# ppc_cpld.net
KiCad netlist of a schematic drawn in Altium Designer
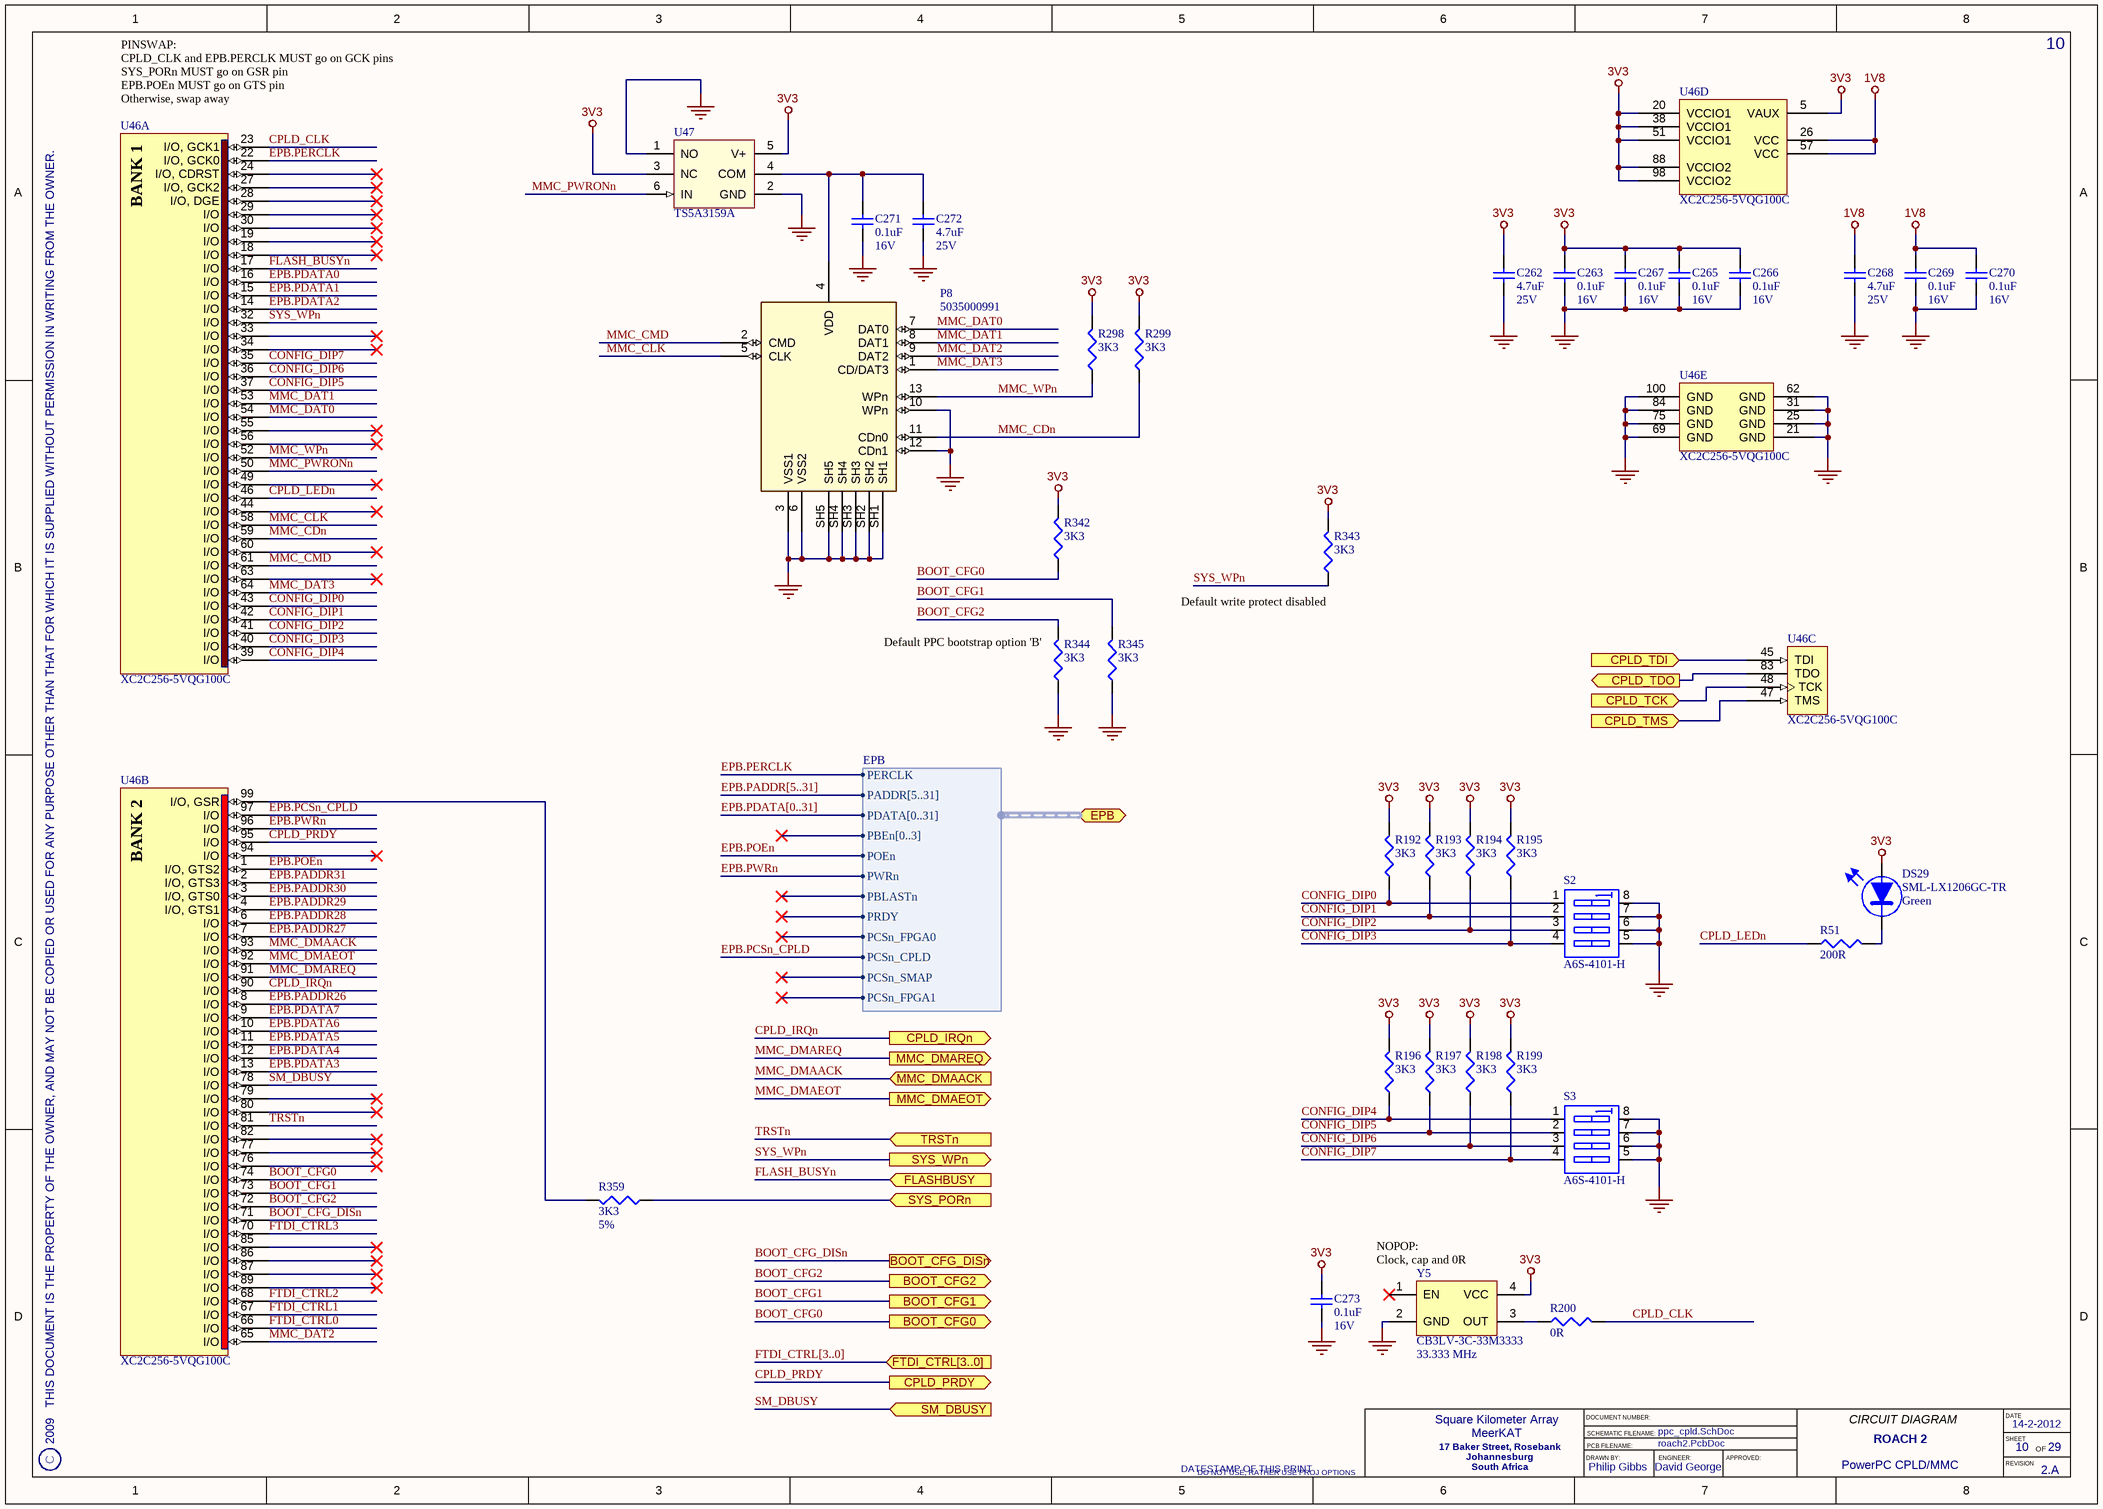
[diagram p0: ppc_cpld.SchDoc]

(export (version "E")
  (design (tool "Eeschema 10.0.6"))
  (components
    (comp (ref "C262")
      (value "4.7uF")
      (footprint "CAPC2012X127L")
      (description "4.7uF, Ceramic Capacitor")
      (fields
        (field (name "RATING") "25V")
        (field (name "MANUFACTURER") "MURATA")
        (field (name "PARTNUM") "GRM21BR61E475KA12K")
      )
      (libsource (lib "altium_db") (part "CapStd"))
    )
    (comp (ref "C263")
      (value "0.1uF")
      (footprint "CAPC1005X60L")
      (description "0.1uF, Ceramic Capacitor")
      (fields
        (field (name "RATING") "16V")
        (field (name "MANUFACTURER") "VENKEL")
        (field (name "PARTNUM") "C0402X7R160-104KN")
      )
      (libsource (lib "altium_db") (part "CapStd"))
    )
    (comp (ref "C265")
      (value "0.1uF")
      (footprint "CAPC1005X60L")
      (description "0.1uF, Ceramic Capacitor")
      (fields
        (field (name "RATING") "16V")
        (field (name "MANUFACTURER") "VENKEL")
        (field (name "PARTNUM") "C0402X7R160-104KN")
      )
      (libsource (lib "altium_db") (part "CapStd"))
    )
    (comp (ref "C266")
      (value "0.1uF")
      (footprint "CAPC1005X60L")
      (description "0.1uF, Ceramic Capacitor")
      (fields
        (field (name "RATING") "16V")
        (field (name "MANUFACTURER") "VENKEL")
        (field (name "PARTNUM") "C0402X7R160-104KN")
      )
      (libsource (lib "altium_db") (part "CapStd"))
    )
    (comp (ref "C267")
      (value "0.1uF")
      (footprint "CAPC1005X60L")
      (description "0.1uF, Ceramic Capacitor")
      (fields
        (field (name "RATING") "16V")
        (field (name "MANUFACTURER") "VENKEL")
        (field (name "PARTNUM") "C0402X7R160-104KN")
      )
      (libsource (lib "altium_db") (part "CapStd"))
    )
    (comp (ref "C268")
      (value "4.7uF")
      (footprint "CAPC2012X127L")
      (description "4.7uF, Ceramic Capacitor")
      (fields
        (field (name "RATING") "25V")
        (field (name "MANUFACTURER") "MURATA")
        (field (name "PARTNUM") "GRM21BR61E475KA12K")
      )
      (libsource (lib "altium_db") (part "CapStd"))
    )
    (comp (ref "C269")
      (value "0.1uF")
      (footprint "CAPC1005X60L")
      (description "0.1uF, Ceramic Capacitor")
      (fields
        (field (name "RATING") "16V")
        (field (name "MANUFACTURER") "VENKEL")
        (field (name "PARTNUM") "C0402X7R160-104KN")
      )
      (libsource (lib "altium_db") (part "CapStd"))
    )
    (comp (ref "C270")
      (value "0.1uF")
      (footprint "CAPC1005X60L")
      (description "0.1uF, Ceramic Capacitor")
      (fields
        (field (name "RATING") "16V")
        (field (name "MANUFACTURER") "VENKEL")
        (field (name "PARTNUM") "C0402X7R160-104KN")
      )
      (libsource (lib "altium_db") (part "CapStd"))
    )
    (comp (ref "C271")
      (value "0.1uF")
      (footprint "CAPC1005X60L")
      (description "0.1uF, Ceramic Capacitor")
      (fields
        (field (name "RATING") "16V")
        (field (name "MANUFACTURER") "VENKEL")
        (field (name "PARTNUM") "C0402X7R160-104KN")
      )
      (libsource (lib "altium_db") (part "CapStd"))
    )
    (comp (ref "C272")
      (value "4.7uF")
      (footprint "CAPC2012X127L")
      (description "4.7uF, Ceramic Capacitor")
      (fields
        (field (name "RATING") "25V")
        (field (name "MANUFACTURER") "MURATA")
        (field (name "PARTNUM") "GRM21BR61E475KA12K")
      )
      (libsource (lib "altium_db") (part "CapStd"))
    )
    (comp (ref "C273")
      (value "0.1uF")
      (footprint "CAPC1005X60L")
      (description "0.1uF, Ceramic Capacitor")
      (fields
        (field (name "RATING") "16V")
        (field (name "MANUFACTURER") "VENKEL")
        (field (name "PARTNUM") "C0402X7R160-104KN")
      )
      (libsource (lib "altium_db") (part "CapStd"))
    )
    (comp (ref "DS29")
      (value "SML-LX1206GC-TR")
      (footprint "LEDC3216X120N")
      (description "Green, Surface mount, LED, 1206")
      (fields (field (name "COLOUR") "Green") (field (name "MANUFACTURER") "LUMEX"))
      (libsource (lib "altium_db") (part "LEDSTD"))
    )
    (comp (ref "P8")
      (value "5035000991")
      (footprint "MOLEX_5035000991")
      (description "Push/Push SD Card Connector with Card Detection")
      (fields (field (name "PARTNUM") "5035000991") (field (name "MANUFACTURER") "Molex"))
      (libsource (lib "altium_db") (part "MOLEX_5035000991"))
    )
    (comp (ref "R51")
      (value "200R")
      (footprint "RESC1005X40L")
      (description "200R, 1.1mm x 0.5mm, Thick Film Resistor")
      (fields (field (name "MANUFACTURER") "ROYALOHM") (field (name "PARTNUM") "0402WGF0201T1E"))
      (libsource (lib "altium_db") (part "ResStd"))
    )
    (comp (ref "R192")
      (value "3K3")
      (footprint "RESC1005X40L")
      (description "3K3, 1.1mm x 0.5mm, Thick Film Resistor")
      (fields (field (name "MANUFACTURER") "ROYALOHM") (field (name "PARTNUM") "0402WGJ0332T1E"))
      (libsource (lib "altium_db") (part "ResStd"))
    )
    (comp (ref "R193")
      (value "3K3")
      (footprint "RESC1005X40L")
      (description "3K3, 1.1mm x 0.5mm, Thick Film Resistor")
      (fields (field (name "MANUFACTURER") "ROYALOHM") (field (name "PARTNUM") "0402WGJ0332T1E"))
      (libsource (lib "altium_db") (part "ResStd"))
    )
    (comp (ref "R194")
      (value "3K3")
      (footprint "RESC1005X40L")
      (description "3K3, 1.1mm x 0.5mm, Thick Film Resistor")
      (fields (field (name "MANUFACTURER") "ROYALOHM") (field (name "PARTNUM") "0402WGJ0332T1E"))
      (libsource (lib "altium_db") (part "ResStd"))
    )
    (comp (ref "R195")
      (value "3K3")
      (footprint "RESC1005X40L")
      (description "3K3, 1.1mm x 0.5mm, Thick Film Resistor")
      (fields (field (name "MANUFACTURER") "ROYALOHM") (field (name "PARTNUM") "0402WGJ0332T1E"))
      (libsource (lib "altium_db") (part "ResStd"))
    )
    (comp (ref "R196")
      (value "3K3")
      (footprint "RESC1005X40L")
      (description "3K3, 1.1mm x 0.5mm, Thick Film Resistor")
      (fields (field (name "MANUFACTURER") "ROYALOHM") (field (name "PARTNUM") "0402WGJ0332T1E"))
      (libsource (lib "altium_db") (part "ResStd"))
    )
    (comp (ref "R197")
      (value "3K3")
      (footprint "RESC1005X40L")
      (description "3K3, 1.1mm x 0.5mm, Thick Film Resistor")
      (fields (field (name "MANUFACTURER") "ROYALOHM") (field (name "PARTNUM") "0402WGJ0332T1E"))
      (libsource (lib "altium_db") (part "ResStd"))
    )
    (comp (ref "R198")
      (value "3K3")
      (footprint "RESC1005X40L")
      (description "3K3, 1.1mm x 0.5mm, Thick Film Resistor")
      (fields (field (name "MANUFACTURER") "ROYALOHM") (field (name "PARTNUM") "0402WGJ0332T1E"))
      (libsource (lib "altium_db") (part "ResStd"))
    )
    (comp (ref "R199")
      (value "3K3")
      (footprint "RESC1005X40L")
      (description "3K3, 1.1mm x 0.5mm, Thick Film Resistor")
      (fields (field (name "MANUFACTURER") "ROYALOHM") (field (name "PARTNUM") "0402WGJ0332T1E"))
      (libsource (lib "altium_db") (part "ResStd"))
    )
    (comp (ref "R200")
      (value "0R")
      (footprint "RESC1005X40L")
      (description "0R, 1.1mm x 0.5mm, Thick Film Resistor")
      (fields (field (name "MANUFACTURER") "ROYALOHM") (field (name "PARTNUM") "0402WG00000T1E"))
      (libsource (lib "altium_db") (part "ResStd"))
    )
    (comp (ref "R298")
      (value "3K3")
      (footprint "RESC1005X40L")
      (description "3K3, 1.1mm x 0.5mm, Thick Film Resistor")
      (fields (field (name "MANUFACTURER") "ROYALOHM") (field (name "PARTNUM") "0402WGJ0332T1E"))
      (libsource (lib "altium_db") (part "ResStd"))
    )
    (comp (ref "R299")
      (value "3K3")
      (footprint "RESC1005X40L")
      (description "3K3, 1.1mm x 0.5mm, Thick Film Resistor")
      (fields (field (name "MANUFACTURER") "ROYALOHM") (field (name "PARTNUM") "0402WGJ0332T1E"))
      (libsource (lib "altium_db") (part "ResStd"))
    )
    (comp (ref "R342")
      (value "3K3")
      (footprint "RESC1005X40L")
      (description "3K3, 1.1mm x 0.5mm, Thick Film Resistor")
      (fields (field (name "MANUFACTURER") "ROYALOHM") (field (name "PARTNUM") "0402WGJ0332T1E"))
      (libsource (lib "altium_db") (part "ResStd"))
    )
    (comp (ref "R343")
      (value "3K3")
      (footprint "RESC1005X40L")
      (description "3K3, 1.1mm x 0.5mm, Thick Film Resistor")
      (fields (field (name "MANUFACTURER") "ROYALOHM") (field (name "PARTNUM") "0402WGJ0332T1E"))
      (libsource (lib "altium_db") (part "ResStd"))
    )
    (comp (ref "R344")
      (value "3K3")
      (footprint "RESC1005X40L")
      (description "3K3, 1.1mm x 0.5mm, Thick Film Resistor")
      (fields (field (name "MANUFACTURER") "ROYALOHM") (field (name "PARTNUM") "0402WGJ0332T1E"))
      (libsource (lib "altium_db") (part "ResStd"))
    )
    (comp (ref "R345")
      (value "3K3")
      (footprint "RESC1005X40L")
      (description "3K3, 1.1mm x 0.5mm, Thick Film Resistor")
      (fields (field (name "MANUFACTURER") "ROYALOHM") (field (name "PARTNUM") "0402WGJ0332T1E"))
      (libsource (lib "altium_db") (part "ResStd"))
    )
    (comp (ref "R359")
      (value "3K3")
      (footprint "RESC1005X40L")
      (description "3K3, 1.1mm x 0.5mm, Thick Film Resistor")
      (fields
        (field (name "MANUFACTURER") "ROYALOHM")
        (field (name "PARTNUM") "0402WGJ0332T1E")
        (field (name "TOLERANCE") "5%")
      )
      (libsource (lib "altium_db") (part "ResStd"))
    )
    (comp (ref "S2")
      (value "A6S-4101-H")
      (footprint "A6S-4101-H")
      (description "4-Input, Surface mount, DIP Switch")
      (fields (field (name "PARTNUM") "A6S-4101-H") (field (name "MANUFACTURER") "OMRON"))
      (libsource (lib "altium_db") (part "A6S-4101-H"))
    )
    (comp (ref "S3")
      (value "A6S-4101-H")
      (footprint "A6S-4101-H")
      (description "4-Input, Surface mount, DIP Switch")
      (fields (field (name "PARTNUM") "A6S-4101-H") (field (name "MANUFACTURER") "OMRON"))
      (libsource (lib "altium_db") (part "A6S-4101-H"))
    )
    (comp (ref "U46")
      (value "XC2C256-5VQG100C")
      (footprint "VQG100_L")
      (description "CoolRunner-II, 1.8V, 256 Macrocell CPLD, 100-Pin VQFP, Pb-Free, Commercial Grade")
      (fields (field (name "MANUFACTURER") "Xilinx"))
      (libsource (lib "altium_db") (part "XC2C256-5VQG100C"))
    )
    (comp (ref "U47")
      (value "TS5A3159A")
      (footprint "SOT23-6")
      (description "6-pin 1 Ohm analogue switch")
      (fields (field (name "MANUFACTURER") "Texas Instruments"))
      (libsource (lib "altium_db") (part "TS5A3159A"))
    )
    (comp (ref "Y5")
      (value "CB3LV-3C-33M3333")
      (footprint "CB3X-X-XMX")
      (description "Surface mount, 33.3333 MHz, 3V3 Clock, oscillator")
      (fields
        (field (name "PARTNUM") "CB3LV-3C-33M3333")
        (field (name "FREQUENCY") "33.333 MHz")
        (field (name "MANUFACTURER") "CTS")
      )
      (libsource (lib "altium_db") (part "CB3LV-3C-33M3333"))
    )
  )
  (nets
    (net (code "48") (name "/BOOT_CFG0") (class "Default")
      (node (ref "R342") (pin "1") (pinfunction "1_1") (pintype "passive"))
      (node (ref "U46") (pin "74") (pinfunction "I/O_74") (pintype "bidirectional"))
    )
    (net (code "49") (name "/BOOT_CFG1") (class "Default")
      (node (ref "R345") (pin "2") (pinfunction "2_2") (pintype "passive"))
      (node (ref "U46") (pin "73") (pinfunction "I/O_73") (pintype "bidirectional"))
    )
    (net (code "50") (name "/BOOT_CFG2") (class "Default")
      (node (ref "R344") (pin "2") (pinfunction "2_2") (pintype "passive"))
      (node (ref "U46") (pin "72") (pinfunction "I/O_72") (pintype "bidirectional"))
    )
    (net (code "51") (name "/BOOT_CFG_DISn") (class "Default")
      (node (ref "U46") (pin "71") (pinfunction "I/O_71") (pintype "bidirectional"))
    )
    (net (code "52") (name "/CONFIG_DIP0") (class "Default")
      (node (ref "R192") (pin "1") (pinfunction "1_1") (pintype "passive"))
      (node (ref "S2") (pin "1") (pinfunction "SW1A_1") (pintype "passive"))
      (node (ref "U46") (pin "43") (pinfunction "I/O_43") (pintype "bidirectional"))
    )
    (net (code "53") (name "/CONFIG_DIP1") (class "Default")
      (node (ref "R193") (pin "1") (pinfunction "1_1") (pintype "passive"))
      (node (ref "S2") (pin "2") (pinfunction "SW2A_2") (pintype "passive"))
      (node (ref "U46") (pin "42") (pinfunction "I/O_42") (pintype "bidirectional"))
    )
    (net (code "54") (name "/CONFIG_DIP2") (class "Default")
      (node (ref "R194") (pin "1") (pinfunction "1_1") (pintype "passive"))
      (node (ref "S2") (pin "3") (pinfunction "SW3A_3") (pintype "passive"))
      (node (ref "U46") (pin "41") (pinfunction "I/O_41") (pintype "bidirectional"))
    )
    (net (code "55") (name "/CONFIG_DIP3") (class "Default")
      (node (ref "R195") (pin "1") (pinfunction "1_1") (pintype "passive"))
      (node (ref "S2") (pin "4") (pinfunction "SW4A_4") (pintype "passive"))
      (node (ref "U46") (pin "40") (pinfunction "I/O_40") (pintype "bidirectional"))
    )
    (net (code "56") (name "/CONFIG_DIP4") (class "Default")
      (node (ref "R196") (pin "1") (pinfunction "1_1") (pintype "passive"))
      (node (ref "S3") (pin "1") (pinfunction "SW1A_1") (pintype "passive"))
      (node (ref "U46") (pin "39") (pinfunction "I/O_39") (pintype "bidirectional"))
    )
    (net (code "57") (name "/CONFIG_DIP5") (class "Default")
      (node (ref "R197") (pin "1") (pinfunction "1_1") (pintype "passive"))
      (node (ref "S3") (pin "2") (pinfunction "SW2A_2") (pintype "passive"))
      (node (ref "U46") (pin "37") (pinfunction "I/O_37") (pintype "bidirectional"))
    )
    (net (code "58") (name "/CONFIG_DIP6") (class "Default")
      (node (ref "R198") (pin "1") (pinfunction "1_1") (pintype "passive"))
      (node (ref "S3") (pin "3") (pinfunction "SW3A_3") (pintype "passive"))
      (node (ref "U46") (pin "36") (pinfunction "I/O_36") (pintype "bidirectional"))
    )
    (net (code "59") (name "/CONFIG_DIP7") (class "Default")
      (node (ref "R199") (pin "1") (pinfunction "1_1") (pintype "passive"))
      (node (ref "S3") (pin "4") (pinfunction "SW4A_4") (pintype "passive"))
      (node (ref "U46") (pin "35") (pinfunction "I/O_35") (pintype "bidirectional"))
    )
    (net (code "60") (name "/CPLD_CLK") (class "Default")
      (node (ref "R200") (pin "2") (pinfunction "2_2") (pintype "passive"))
      (node (ref "U46") (pin "23") (pinfunction "I/O,_GCK1_23") (pintype "bidirectional"))
    )
    (net (code "61") (name "/CPLD_IRQn") (class "Default")
      (node (ref "U46") (pin "90") (pinfunction "I/O_90") (pintype "bidirectional"))
    )
    (net (code "62") (name "/CPLD_LEDn") (class "Default")
      (node (ref "R51") (pin "1") (pinfunction "1_1") (pintype "passive"))
      (node (ref "U46") (pin "46") (pinfunction "I/O_46") (pintype "bidirectional"))
    )
    (net (code "63") (name "/CPLD_PRDY") (class "Default")
      (node (ref "U46") (pin "95") (pinfunction "I/O_95") (pintype "bidirectional"))
    )
    (net (code "64") (name "/CPLD_TCK") (class "Default")
      (node (ref "U46") (pin "48") (pinfunction "TCK_48") (pintype "input"))
    )
    (net (code "65") (name "/CPLD_TDI") (class "Default")
      (node (ref "U46") (pin "45") (pinfunction "TDI_45") (pintype "input"))
    )
    (net (code "66") (name "/CPLD_TDO") (class "Default")
      (node (ref "U46") (pin "83") (pinfunction "TDO_83") (pintype "passive"))
    )
    (net (code "67") (name "/CPLD_TMS") (class "Default")
      (node (ref "U46") (pin "47") (pinfunction "TMS_47") (pintype "input"))
    )
    (net (code "68") (name "/EPB.PADDR26") (class "Default")
      (node (ref "U46") (pin "8") (pinfunction "I/O_8") (pintype "bidirectional"))
    )
    (net (code "69") (name "/EPB.PADDR27") (class "Default")
      (node (ref "U46") (pin "7") (pinfunction "I/O_7") (pintype "bidirectional"))
    )
    (net (code "70") (name "/EPB.PADDR28") (class "Default")
      (node (ref "U46") (pin "6") (pinfunction "I/O_6") (pintype "bidirectional"))
    )
    (net (code "71") (name "/EPB.PADDR29") (class "Default")
      (node (ref "U46") (pin "4") (pinfunction "I/O,_GTS1_4") (pintype "bidirectional"))
    )
    (net (code "72") (name "/EPB.PADDR30") (class "Default")
      (node (ref "U46") (pin "3") (pinfunction "I/O,_GTS0_3") (pintype "bidirectional"))
    )
    (net (code "73") (name "/EPB.PADDR31") (class "Default")
      (node (ref "U46") (pin "2") (pinfunction "I/O,_GTS3_2") (pintype "bidirectional"))
    )
    (net (code "75") (name "/EPB.PCSn_CPLD") (class "Default")
      (node (ref "U46") (pin "97") (pinfunction "I/O_97") (pintype "bidirectional"))
    )
    (net (code "76") (name "/EPB.PDATA0") (class "Default")
      (node (ref "U46") (pin "16") (pinfunction "I/O_16") (pintype "bidirectional"))
    )
    (net (code "77") (name "/EPB.PDATA1") (class "Default")
      (node (ref "U46") (pin "15") (pinfunction "I/O_15") (pintype "bidirectional"))
    )
    (net (code "78") (name "/EPB.PDATA2") (class "Default")
      (node (ref "U46") (pin "14") (pinfunction "I/O_14") (pintype "bidirectional"))
    )
    (net (code "79") (name "/EPB.PDATA3") (class "Default")
      (node (ref "U46") (pin "13") (pinfunction "I/O_13") (pintype "bidirectional"))
    )
    (net (code "80") (name "/EPB.PDATA4") (class "Default")
      (node (ref "U46") (pin "12") (pinfunction "I/O_12") (pintype "bidirectional"))
    )
    (net (code "81") (name "/EPB.PDATA5") (class "Default")
      (node (ref "U46") (pin "11") (pinfunction "I/O_11") (pintype "bidirectional"))
    )
    (net (code "82") (name "/EPB.PDATA6") (class "Default")
      (node (ref "U46") (pin "10") (pinfunction "I/O_10") (pintype "bidirectional"))
    )
    (net (code "83") (name "/EPB.PDATA7") (class "Default")
      (node (ref "U46") (pin "9") (pinfunction "I/O_9") (pintype "bidirectional"))
    )
    (net (code "85") (name "/EPB.PERCLK") (class "Default")
      (node (ref "U46") (pin "22") (pinfunction "I/O,_GCK0_22") (pintype "bidirectional"))
    )
    (net (code "86") (name "/EPB.POEn") (class "Default")
      (node (ref "U46") (pin "1") (pinfunction "I/O,_GTS2_1") (pintype "bidirectional"))
    )
    (net (code "87") (name "/EPB.PWRn") (class "Default")
      (node (ref "U46") (pin "96") (pinfunction "I/O_96") (pintype "bidirectional"))
    )
    (net (code "89") (name "/FLASH_BUSYn") (class "Default")
      (node (ref "U46") (pin "17") (pinfunction "I/O_17") (pintype "bidirectional"))
    )
    (net (code "90") (name "/FTDI_CTRL0") (class "Default")
      (node (ref "U46") (pin "66") (pinfunction "I/O_66") (pintype "bidirectional"))
    )
    (net (code "91") (name "/FTDI_CTRL1") (class "Default")
      (node (ref "U46") (pin "67") (pinfunction "I/O_67") (pintype "bidirectional"))
    )
    (net (code "92") (name "/FTDI_CTRL2") (class "Default")
      (node (ref "U46") (pin "68") (pinfunction "I/O_68") (pintype "bidirectional"))
    )
    (net (code "93") (name "/FTDI_CTRL3") (class "Default")
      (node (ref "U46") (pin "70") (pinfunction "I/O_70") (pintype "bidirectional"))
    )
    (net (code "95") (name "/MMC_CDn") (class "Default")
      (node (ref "P8") (pin "11") (pinfunction "CDn0_11") (pintype "bidirectional"))
      (node (ref "R299") (pin "1") (pinfunction "1_1") (pintype "passive"))
      (node (ref "U46") (pin "59") (pinfunction "I/O_59") (pintype "bidirectional"))
    )
    (net (code "96") (name "/MMC_CLK") (class "Default")
      (node (ref "P8") (pin "5") (pinfunction "CLK_5") (pintype "bidirectional"))
      (node (ref "U46") (pin "58") (pinfunction "I/O_58") (pintype "bidirectional"))
    )
    (net (code "97") (name "/MMC_CMD") (class "Default")
      (node (ref "P8") (pin "2") (pinfunction "CMD_2") (pintype "bidirectional"))
      (node (ref "U46") (pin "61") (pinfunction "I/O_61") (pintype "bidirectional"))
    )
    (net (code "98") (name "/MMC_DAT0") (class "Default")
      (node (ref "P8") (pin "7") (pinfunction "DAT0_7") (pintype "bidirectional"))
      (node (ref "U46") (pin "54") (pinfunction "I/O_54") (pintype "bidirectional"))
    )
    (net (code "99") (name "/MMC_DAT1") (class "Default")
      (node (ref "P8") (pin "8") (pinfunction "DAT1_8") (pintype "bidirectional"))
      (node (ref "U46") (pin "53") (pinfunction "I/O_53") (pintype "bidirectional"))
    )
    (net (code "100") (name "/MMC_DAT2") (class "Default")
      (node (ref "P8") (pin "9") (pinfunction "DAT2_9") (pintype "bidirectional"))
      (node (ref "U46") (pin "65") (pinfunction "I/O_65") (pintype "bidirectional"))
    )
    (net (code "101") (name "/MMC_DAT3") (class "Default")
      (node (ref "P8") (pin "1") (pinfunction "CD/DAT3_1") (pintype "bidirectional"))
      (node (ref "U46") (pin "64") (pinfunction "I/O_64") (pintype "bidirectional"))
    )
    (net (code "102") (name "/MMC_DMAACK") (class "Default")
      (node (ref "U46") (pin "93") (pinfunction "I/O_93") (pintype "bidirectional"))
    )
    (net (code "103") (name "/MMC_DMAEOT") (class "Default")
      (node (ref "U46") (pin "92") (pinfunction "I/O_92") (pintype "bidirectional"))
    )
    (net (code "104") (name "/MMC_DMAREQ") (class "Default")
      (node (ref "U46") (pin "91") (pinfunction "I/O_91") (pintype "bidirectional"))
    )
    (net (code "105") (name "/MMC_PWRONn") (class "Default")
      (node (ref "U46") (pin "50") (pinfunction "I/O_50") (pintype "bidirectional"))
      (node (ref "U47") (pin "6") (pinfunction "IN_6") (pintype "input"))
    )
    (net (code "106") (name "/MMC_WPn") (class "Default")
      (node (ref "P8") (pin "13") (pinfunction "WPn_13") (pintype "bidirectional"))
      (node (ref "R298") (pin "1") (pinfunction "1_1") (pintype "passive"))
      (node (ref "U46") (pin "52") (pinfunction "I/O_52") (pintype "bidirectional"))
    )
    (net (code "107") (name "/SM_DBUSY") (class "Default")
      (node (ref "U46") (pin "78") (pinfunction "I/O_78") (pintype "bidirectional"))
    )
    (net (code "108") (name "/SYS_PORn") (class "Default")
      (node (ref "R359") (pin "1") (pinfunction "1_1") (pintype "passive"))
    )
    (net (code "109") (name "/SYS_WPn") (class "Default")
      (node (ref "R343") (pin "1") (pinfunction "1_1") (pintype "passive"))
      (node (ref "U46") (pin "32") (pinfunction "I/O_32") (pintype "bidirectional"))
    )
    (net (code "110") (name "/TRSTn") (class "Default")
      (node (ref "U46") (pin "81") (pinfunction "I/O_81") (pintype "bidirectional"))
    )
    (net (code "112") (name "1V8") (class "Default")
      (node (ref "C268") (pin "2") (pinfunction "2_2") (pintype "passive"))
      (node (ref "C269") (pin "2") (pinfunction "2_2") (pintype "passive"))
      (node (ref "C270") (pin "2") (pinfunction "2_2") (pintype "passive"))
      (node (ref "U46") (pin "26") (pinfunction "VCC_26") (pintype "power_in"))
      (node (ref "U46") (pin "57") (pinfunction "VCC_57") (pintype "power_in"))
    )
    (net (code "113") (name "3V3") (class "Default")
      (node (ref "C262") (pin "2") (pinfunction "2_2") (pintype "passive"))
      (node (ref "C263") (pin "2") (pinfunction "2_2") (pintype "passive"))
      (node (ref "C265") (pin "2") (pinfunction "2_2") (pintype "passive"))
      (node (ref "C266") (pin "2") (pinfunction "2_2") (pintype "passive"))
      (node (ref "C267") (pin "2") (pinfunction "2_2") (pintype "passive"))
      (node (ref "C273") (pin "2") (pinfunction "2_2") (pintype "passive"))
      (node (ref "DS29") (pin "2") (pinfunction "A_2") (pintype "passive"))
      (node (ref "R192") (pin "2") (pinfunction "2_2") (pintype "passive"))
      (node (ref "R193") (pin "2") (pinfunction "2_2") (pintype "passive"))
      (node (ref "R194") (pin "2") (pinfunction "2_2") (pintype "passive"))
      (node (ref "R195") (pin "2") (pinfunction "2_2") (pintype "passive"))
      (node (ref "R196") (pin "2") (pinfunction "2_2") (pintype "passive"))
      (node (ref "R197") (pin "2") (pinfunction "2_2") (pintype "passive"))
      (node (ref "R198") (pin "2") (pinfunction "2_2") (pintype "passive"))
      (node (ref "R199") (pin "2") (pinfunction "2_2") (pintype "passive"))
      (node (ref "R298") (pin "2") (pinfunction "2_2") (pintype "passive"))
      (node (ref "R299") (pin "2") (pinfunction "2_2") (pintype "passive"))
      (node (ref "R342") (pin "2") (pinfunction "2_2") (pintype "passive"))
      (node (ref "R343") (pin "2") (pinfunction "2_2") (pintype "passive"))
      (node (ref "U46") (pin "20") (pinfunction "VCCIO1_20") (pintype "power_in"))
      (node (ref "U46") (pin "38") (pinfunction "VCCIO1_38") (pintype "power_in"))
      (node (ref "U46") (pin "5") (pinfunction "VAUX_5") (pintype "power_in"))
      (node (ref "U46") (pin "51") (pinfunction "VCCIO1_51") (pintype "power_in"))
      (node (ref "U46") (pin "88") (pinfunction "VCCIO2_88") (pintype "power_in"))
      (node (ref "U46") (pin "98") (pinfunction "VCCIO2_98") (pintype "power_in"))
      (node (ref "U47") (pin "3") (pinfunction "NC_3") (pintype "passive"))
      (node (ref "U47") (pin "5") (pinfunction "V+_5") (pintype "passive"))
      (node (ref "Y5") (pin "4") (pinfunction "VCC_4") (pintype "passive"))
    )
    (net (code "114") (name "GND") (class "Default")
      (node (ref "C262") (pin "1") (pinfunction "1_1") (pintype "passive"))
      (node (ref "C263") (pin "1") (pinfunction "1_1") (pintype "passive"))
      (node (ref "C265") (pin "1") (pinfunction "1_1") (pintype "passive"))
      (node (ref "C266") (pin "1") (pinfunction "1_1") (pintype "passive"))
      (node (ref "C267") (pin "1") (pinfunction "1_1") (pintype "passive"))
      (node (ref "C268") (pin "1") (pinfunction "1_1") (pintype "passive"))
      (node (ref "C269") (pin "1") (pinfunction "1_1") (pintype "passive"))
      (node (ref "C270") (pin "1") (pinfunction "1_1") (pintype "passive"))
      (node (ref "C271") (pin "1") (pinfunction "1_1") (pintype "passive"))
      (node (ref "C272") (pin "1") (pinfunction "1_1") (pintype "passive"))
      (node (ref "C273") (pin "1") (pinfunction "1_1") (pintype "passive"))
      (node (ref "P8") (pin "10") (pinfunction "WPn_10") (pintype "bidirectional"))
      (node (ref "P8") (pin "12") (pinfunction "CDn1_12") (pintype "bidirectional"))
      (node (ref "P8") (pin "3") (pinfunction "VSS1_3") (pintype "power_in"))
      (node (ref "P8") (pin "6") (pinfunction "VSS2_6") (pintype "power_in"))
      (node (ref "P8") (pin "SH1") (pinfunction "SH1_SH1") (pintype "power_in"))
      (node (ref "P8") (pin "SH2") (pinfunction "SH2_SH2") (pintype "power_in"))
      (node (ref "P8") (pin "SH3") (pinfunction "SH3_SH3") (pintype "power_in"))
      (node (ref "P8") (pin "SH4") (pinfunction "SH4_SH4") (pintype "power_in"))
      (node (ref "P8") (pin "SH5") (pinfunction "SH5_SH5") (pintype "power_in"))
      (node (ref "R344") (pin "1") (pinfunction "1_1") (pintype "passive"))
      (node (ref "R345") (pin "1") (pinfunction "1_1") (pintype "passive"))
      (node (ref "S2") (pin "5") (pinfunction "SW4B_5") (pintype "passive"))
      (node (ref "S2") (pin "6") (pinfunction "SW3B_6") (pintype "passive"))
      (node (ref "S2") (pin "7") (pinfunction "SW2B_7") (pintype "passive"))
      (node (ref "S2") (pin "8") (pinfunction "SW1B_8") (pintype "passive"))
      (node (ref "S3") (pin "5") (pinfunction "SW4B_5") (pintype "passive"))
      (node (ref "S3") (pin "6") (pinfunction "SW3B_6") (pintype "passive"))
      (node (ref "S3") (pin "7") (pinfunction "SW2B_7") (pintype "passive"))
      (node (ref "S3") (pin "8") (pinfunction "SW1B_8") (pintype "passive"))
      (node (ref "U46") (pin "100") (pinfunction "GND_100") (pintype "power_in"))
      (node (ref "U46") (pin "21") (pinfunction "GND_21") (pintype "power_in"))
      (node (ref "U46") (pin "25") (pinfunction "GND_25") (pintype "power_in"))
      (node (ref "U46") (pin "31") (pinfunction "GND_31") (pintype "power_in"))
      (node (ref "U46") (pin "62") (pinfunction "GND_62") (pintype "power_in"))
      (node (ref "U46") (pin "69") (pinfunction "GND_69") (pintype "power_in"))
      (node (ref "U46") (pin "75") (pinfunction "GND_75") (pintype "power_in"))
      (node (ref "U46") (pin "84") (pinfunction "GND_84") (pintype "power_in"))
      (node (ref "U47") (pin "1") (pinfunction "NO_1") (pintype "passive"))
      (node (ref "U47") (pin "2") (pinfunction "GND_2") (pintype "passive"))
      (node (ref "Y5") (pin "2") (pinfunction "GND_2") (pintype "passive"))
    )
    (net (code "115") (name "Net-(DS29-K)") (class "Default")
      (node (ref "DS29") (pin "1") (pinfunction "K_1") (pintype "passive"))
      (node (ref "R51") (pin "2") (pinfunction "2_2") (pintype "passive"))
    )
    (net (code "116") (name "Net-(P8-VDD)") (class "Default")
      (node (ref "C271") (pin "2") (pinfunction "2_2") (pintype "passive"))
      (node (ref "C272") (pin "2") (pinfunction "2_2") (pintype "passive"))
      (node (ref "P8") (pin "4") (pinfunction "VDD_4") (pintype "power_in"))
      (node (ref "U47") (pin "4") (pinfunction "COM_4") (pintype "passive"))
    )
    (net (code "117") (name "Net-(U46B-I{slash}O,_GSR)") (class "Default")
      (node (ref "R359") (pin "2") (pinfunction "2_2") (pintype "passive"))
      (node (ref "U46") (pin "99") (pinfunction "I/O,_GSR_99") (pintype "bidirectional"))
    )
    (net (code "118") (name "Net-(Y5-OUT)") (class "Default")
      (node (ref "R200") (pin "1") (pinfunction "1_1") (pintype "passive"))
      (node (ref "Y5") (pin "3") (pinfunction "OUT_3") (pintype "passive"))
    )
    (net (code "119") (name "unconnected-(U46A-I{slash}O,_CDRST-Pad24)") (class "Default")
      (node (ref "U46") (pin "24") (pinfunction "I/O,_CDRST_24") (pintype "bidirectional+no_connect"))
    )
    (net (code "120") (name "unconnected-(U46A-I{slash}O,_DGE-Pad28)") (class "Default")
      (node (ref "U46") (pin "28") (pinfunction "I/O,_DGE_28") (pintype "bidirectional+no_connect"))
    )
    (net (code "121") (name "unconnected-(U46A-I{slash}O,_GCK2-Pad27)") (class "Default")
      (node (ref "U46") (pin "27") (pinfunction "I/O,_GCK2_27") (pintype "bidirectional+no_connect"))
    )
    (net (code "122") (name "unconnected-(U46A-I{slash}O-Pad18)") (class "Default")
      (node (ref "U46") (pin "18") (pinfunction "I/O_18") (pintype "bidirectional+no_connect"))
    )
    (net (code "123") (name "unconnected-(U46A-I{slash}O-Pad19)") (class "Default")
      (node (ref "U46") (pin "19") (pinfunction "I/O_19") (pintype "bidirectional+no_connect"))
    )
    (net (code "124") (name "unconnected-(U46A-I{slash}O-Pad29)") (class "Default")
      (node (ref "U46") (pin "29") (pinfunction "I/O_29") (pintype "bidirectional+no_connect"))
    )
    (net (code "125") (name "unconnected-(U46A-I{slash}O-Pad30)") (class "Default")
      (node (ref "U46") (pin "30") (pinfunction "I/O_30") (pintype "bidirectional+no_connect"))
    )
    (net (code "126") (name "unconnected-(U46A-I{slash}O-Pad33)") (class "Default")
      (node (ref "U46") (pin "33") (pinfunction "I/O_33") (pintype "bidirectional+no_connect"))
    )
    (net (code "127") (name "unconnected-(U46A-I{slash}O-Pad34)") (class "Default")
      (node (ref "U46") (pin "34") (pinfunction "I/O_34") (pintype "bidirectional+no_connect"))
    )
    (net (code "128") (name "unconnected-(U46A-I{slash}O-Pad44)") (class "Default")
      (node (ref "U46") (pin "44") (pinfunction "I/O_44") (pintype "bidirectional+no_connect"))
    )
    (net (code "129") (name "unconnected-(U46A-I{slash}O-Pad49)") (class "Default")
      (node (ref "U46") (pin "49") (pinfunction "I/O_49") (pintype "bidirectional+no_connect"))
    )
    (net (code "130") (name "unconnected-(U46A-I{slash}O-Pad55)") (class "Default")
      (node (ref "U46") (pin "55") (pinfunction "I/O_55") (pintype "bidirectional+no_connect"))
    )
    (net (code "131") (name "unconnected-(U46A-I{slash}O-Pad56)") (class "Default")
      (node (ref "U46") (pin "56") (pinfunction "I/O_56") (pintype "bidirectional+no_connect"))
    )
    (net (code "132") (name "unconnected-(U46A-I{slash}O-Pad60)") (class "Default")
      (node (ref "U46") (pin "60") (pinfunction "I/O_60") (pintype "bidirectional+no_connect"))
    )
    (net (code "133") (name "unconnected-(U46A-I{slash}O-Pad63)") (class "Default")
      (node (ref "U46") (pin "63") (pinfunction "I/O_63") (pintype "bidirectional+no_connect"))
    )
    (net (code "134") (name "unconnected-(U46B-I{slash}O-Pad76)") (class "Default")
      (node (ref "U46") (pin "76") (pinfunction "I/O_76") (pintype "bidirectional+no_connect"))
    )
    (net (code "135") (name "unconnected-(U46B-I{slash}O-Pad77)") (class "Default")
      (node (ref "U46") (pin "77") (pinfunction "I/O_77") (pintype "bidirectional+no_connect"))
    )
    (net (code "136") (name "unconnected-(U46B-I{slash}O-Pad79)") (class "Default")
      (node (ref "U46") (pin "79") (pinfunction "I/O_79") (pintype "bidirectional+no_connect"))
    )
    (net (code "137") (name "unconnected-(U46B-I{slash}O-Pad80)") (class "Default")
      (node (ref "U46") (pin "80") (pinfunction "I/O_80") (pintype "bidirectional+no_connect"))
    )
    (net (code "138") (name "unconnected-(U46B-I{slash}O-Pad82)") (class "Default")
      (node (ref "U46") (pin "82") (pinfunction "I/O_82") (pintype "bidirectional+no_connect"))
    )
    (net (code "139") (name "unconnected-(U46B-I{slash}O-Pad85)") (class "Default")
      (node (ref "U46") (pin "85") (pinfunction "I/O_85") (pintype "bidirectional+no_connect"))
    )
    (net (code "140") (name "unconnected-(U46B-I{slash}O-Pad86)") (class "Default")
      (node (ref "U46") (pin "86") (pinfunction "I/O_86") (pintype "bidirectional+no_connect"))
    )
    (net (code "141") (name "unconnected-(U46B-I{slash}O-Pad87)") (class "Default")
      (node (ref "U46") (pin "87") (pinfunction "I/O_87") (pintype "bidirectional+no_connect"))
    )
    (net (code "142") (name "unconnected-(U46B-I{slash}O-Pad89)") (class "Default")
      (node (ref "U46") (pin "89") (pinfunction "I/O_89") (pintype "bidirectional+no_connect"))
    )
    (net (code "143") (name "unconnected-(U46B-I{slash}O-Pad94)") (class "Default")
      (node (ref "U46") (pin "94") (pinfunction "I/O_94") (pintype "bidirectional+no_connect"))
    )
    (net (code "144") (name "unconnected-(Y5-EN-Pad1)") (class "Default")
      (node (ref "Y5") (pin "1") (pinfunction "EN_1") (pintype "passive+no_connect"))
    )
  )
)
